# EasyDriverTip122.net
KiCad netlist of a schematic drawn in EAGLE
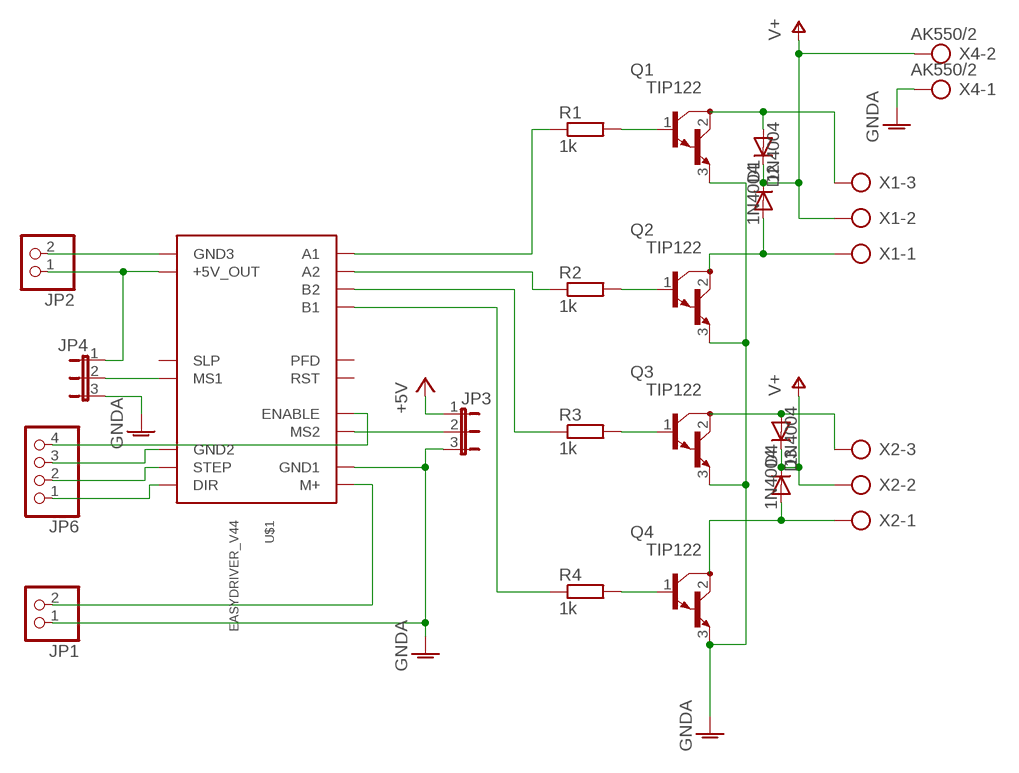
[diagram p0: schematic, sheet 1]

(export (version "E")
  (design (tool "Eeschema 10.0.6"))
  (components
    (comp (ref "D1")
      (value "1N4004")
      (footprint "eagle-import:DO41-10")
      (libsource (lib "eagle-import") (part "1N4004"))
    )
    (comp (ref "D2")
      (value "1N4004")
      (footprint "eagle-import:DO41-10")
      (libsource (lib "eagle-import") (part "1N4004"))
    )
    (comp (ref "D3")
      (value "1N4004")
      (footprint "eagle-import:DO41-10")
      (libsource (lib "eagle-import") (part "1N4004"))
    )
    (comp (ref "D4")
      (value "1N4004")
      (footprint "eagle-import:DO41-10")
      (libsource (lib "eagle-import") (part "1N4004"))
    )
    (comp (ref "JP1")
      (value "PINHD-1X2")
      (footprint "eagle-import:1X02")
      (libsource (lib "eagle-import") (part "PINHD-1X2"))
    )
    (comp (ref "JP2")
      (value "PINHD-1X2")
      (footprint "eagle-import:1X02")
      (libsource (lib "eagle-import") (part "PINHD-1X2"))
    )
    (comp (ref "JP3")
      (value "JP2E")
      (footprint "eagle-import:JP2")
      (libsource (lib "eagle-import") (part "JP2E"))
    )
    (comp (ref "JP4")
      (value "JP2E")
      (footprint "eagle-import:JP2")
      (libsource (lib "eagle-import") (part "JP2E"))
    )
    (comp (ref "JP6")
      (value "PINHD-1X4")
      (footprint "eagle-import:1X04")
      (libsource (lib "eagle-import") (part "PINHD-1X4"))
    )
    (comp (ref "Q1")
      (value "TIP122")
      (footprint "eagle-import:TO220V")
      (libsource (lib "eagle-import") (part "TIP122"))
    )
    (comp (ref "Q2")
      (value "TIP122")
      (footprint "eagle-import:TO220V")
      (libsource (lib "eagle-import") (part "TIP122"))
    )
    (comp (ref "Q3")
      (value "TIP122")
      (footprint "eagle-import:TO220V")
      (libsource (lib "eagle-import") (part "TIP122"))
    )
    (comp (ref "Q4")
      (value "TIP122")
      (footprint "eagle-import:TO220V")
      (libsource (lib "eagle-import") (part "TIP122"))
    )
    (comp (ref "R1")
      (value "1k")
      (footprint "eagle-import:0204_7")
      (libsource (lib "eagle-import") (part "R-EU_0204/7"))
    )
    (comp (ref "R2")
      (value "1k")
      (footprint "eagle-import:0204_7")
      (libsource (lib "eagle-import") (part "R-EU_0204/7"))
    )
    (comp (ref "R3")
      (value "1k")
      (footprint "eagle-import:0204_7")
      (libsource (lib "eagle-import") (part "R-EU_0204/7"))
    )
    (comp (ref "R4")
      (value "1k")
      (footprint "eagle-import:0204_7")
      (libsource (lib "eagle-import") (part "R-EU_0204/7"))
    )
    (comp (ref "U$1")
      (value "EASYDRIVER_V44")
      (footprint "eagle-import:EASYDRIVER_V44")
      (libsource (lib "eagle-import") (part "EASYDRIVER_V44"))
    )
    (comp (ref "X1")
      (value "AK500/3")
      (footprint "eagle-import:AK500_3")
      (libsource (lib "eagle-import") (part "AK500/3"))
    )
    (comp (ref "X2")
      (value "AK500/3")
      (footprint "eagle-import:AK500_3")
      (libsource (lib "eagle-import") (part "AK500/3"))
    )
    (comp (ref "X4")
      (value "AK550/2")
      (footprint "eagle-import:AK550_2")
      (libsource (lib "eagle-import") (part "AK550/2"))
    )
  )
  (nets
    (net (code "1") (name "+5V") (class "Default")
      (node (ref "JP2") (pin "1") (pinfunction "1_1") (pintype "passive"))
      (node (ref "JP3") (pin "1") (pinfunction "1_1") (pintype "passive"))
      (node (ref "JP4") (pin "1") (pinfunction "1_1") (pintype "passive"))
      (node (ref "U$1") (pin "P$11") (pinfunction "+5V_OUT_P$11") (pintype "bidirectional"))
    )
    (net (code "2") (name "GNDA") (class "Default")
      (node (ref "JP1") (pin "1") (pinfunction "1_1") (pintype "passive"))
      (node (ref "JP3") (pin "3") (pinfunction "3_3") (pintype "passive"))
      (node (ref "JP4") (pin "3") (pinfunction "3_3") (pintype "passive"))
      (node (ref "Q1") (pin "3") (pinfunction "E_3") (pintype "passive"))
      (node (ref "Q2") (pin "3") (pinfunction "E_3") (pintype "passive"))
      (node (ref "Q3") (pin "3") (pinfunction "E_3") (pintype "passive"))
      (node (ref "Q4") (pin "3") (pinfunction "E_3") (pintype "passive"))
      (node (ref "U$1") (pin "GND1") (pinfunction "GND1_GND1") (pintype "bidirectional"))
      (node (ref "X4") (pin "1") (pinfunction "KL_1") (pintype "passive"))
    )
    (net (code "3") (name "Net-(JP1-Pad2)") (class "Default")
      (node (ref "JP1") (pin "2") (pinfunction "2_2") (pintype "passive"))
      (node (ref "U$1") (pin "M+") (pinfunction "M+_M+") (pintype "bidirectional"))
    )
    (net (code "4") (name "Net-(JP2-Pad2)") (class "Default")
      (node (ref "JP2") (pin "2") (pinfunction "2_2") (pintype "passive"))
      (node (ref "U$1") (pin "GND3") (pinfunction "GND3_GND3") (pintype "bidirectional"))
    )
    (net (code "5") (name "Net-(JP3-Pad2)") (class "Default")
      (node (ref "JP3") (pin "2") (pinfunction "2_2") (pintype "passive"))
      (node (ref "U$1") (pin "MS2") (pinfunction "MS2_MS2") (pintype "bidirectional"))
    )
    (net (code "6") (name "Net-(JP4-Pad2)") (class "Default")
      (node (ref "JP4") (pin "2") (pinfunction "2_2") (pintype "passive"))
      (node (ref "U$1") (pin "MS1") (pinfunction "MS1_MS1") (pintype "bidirectional"))
    )
    (net (code "7") (name "Net-(JP6-Pad1)") (class "Default")
      (node (ref "JP6") (pin "1") (pinfunction "1_1") (pintype "passive"))
      (node (ref "U$1") (pin "DIR") (pinfunction "DIR_DIR") (pintype "bidirectional"))
    )
    (net (code "8") (name "Net-(JP6-Pad2)") (class "Default")
      (node (ref "JP6") (pin "2") (pinfunction "2_2") (pintype "passive"))
      (node (ref "U$1") (pin "STEP") (pinfunction "STEP_STEP") (pintype "bidirectional"))
    )
    (net (code "9") (name "Net-(JP6-Pad3)") (class "Default")
      (node (ref "JP6") (pin "3") (pinfunction "3_3") (pintype "passive"))
      (node (ref "U$1") (pin "GND2") (pinfunction "GND2_GND2") (pintype "bidirectional"))
    )
    (net (code "10") (name "Net-(JP6-Pad4)") (class "Default")
      (node (ref "JP6") (pin "4") (pinfunction "4_4") (pintype "passive"))
      (node (ref "U$1") (pin "ENABLE") (pinfunction "ENABLE_ENABLE") (pintype "bidirectional"))
    )
    (net (code "11") (name "Net-(Q1-B)") (class "Default")
      (node (ref "Q1") (pin "1") (pinfunction "B_1") (pintype "passive"))
      (node (ref "R1") (pin "2") (pinfunction "2_2") (pintype "passive"))
    )
    (net (code "12") (name "Net-(Q1-C)") (class "Default")
      (node (ref "D2") (pin "A") (pinfunction "A_A") (pintype "passive"))
      (node (ref "Q1") (pin "2") (pinfunction "C_2") (pintype "passive"))
      (node (ref "X1") (pin "3") (pinfunction "KL_3") (pintype "passive"))
    )
    (net (code "13") (name "Net-(Q2-B)") (class "Default")
      (node (ref "Q2") (pin "1") (pinfunction "B_1") (pintype "passive"))
      (node (ref "R2") (pin "2") (pinfunction "2_2") (pintype "passive"))
    )
    (net (code "14") (name "Net-(Q2-C)") (class "Default")
      (node (ref "D1") (pin "A") (pinfunction "A_A") (pintype "passive"))
      (node (ref "Q2") (pin "2") (pinfunction "C_2") (pintype "passive"))
      (node (ref "X1") (pin "1") (pinfunction "KL_1") (pintype "passive"))
    )
    (net (code "15") (name "Net-(Q3-B)") (class "Default")
      (node (ref "Q3") (pin "1") (pinfunction "B_1") (pintype "passive"))
      (node (ref "R3") (pin "2") (pinfunction "2_2") (pintype "passive"))
    )
    (net (code "16") (name "Net-(Q3-C)") (class "Default")
      (node (ref "D3") (pin "A") (pinfunction "A_A") (pintype "passive"))
      (node (ref "Q3") (pin "2") (pinfunction "C_2") (pintype "passive"))
      (node (ref "X2") (pin "3") (pinfunction "KL_3") (pintype "passive"))
    )
    (net (code "17") (name "Net-(Q4-B)") (class "Default")
      (node (ref "Q4") (pin "1") (pinfunction "B_1") (pintype "passive"))
      (node (ref "R4") (pin "2") (pinfunction "2_2") (pintype "passive"))
    )
    (net (code "18") (name "Net-(Q4-C)") (class "Default")
      (node (ref "D4") (pin "A") (pinfunction "A_A") (pintype "passive"))
      (node (ref "Q4") (pin "2") (pinfunction "C_2") (pintype "passive"))
      (node (ref "X2") (pin "1") (pinfunction "KL_1") (pintype "passive"))
    )
    (net (code "19") (name "Net-(R1-Pad1)") (class "Default")
      (node (ref "R1") (pin "1") (pinfunction "1_1") (pintype "passive"))
      (node (ref "U$1") (pin "A1") (pinfunction "A1_A1") (pintype "bidirectional"))
    )
    (net (code "20") (name "Net-(R2-Pad1)") (class "Default")
      (node (ref "R2") (pin "1") (pinfunction "1_1") (pintype "passive"))
      (node (ref "U$1") (pin "A2") (pinfunction "A2_A2") (pintype "bidirectional"))
    )
    (net (code "21") (name "Net-(R3-Pad1)") (class "Default")
      (node (ref "R3") (pin "1") (pinfunction "1_1") (pintype "passive"))
      (node (ref "U$1") (pin "B2") (pinfunction "B2_B2") (pintype "bidirectional"))
    )
    (net (code "22") (name "Net-(R4-Pad1)") (class "Default")
      (node (ref "R4") (pin "1") (pinfunction "1_1") (pintype "passive"))
      (node (ref "U$1") (pin "B1") (pinfunction "B1_B1") (pintype "bidirectional"))
    )
    (net (code "23") (name "V+") (class "Default")
      (node (ref "D1") (pin "C") (pinfunction "C_C") (pintype "passive"))
      (node (ref "D2") (pin "C") (pinfunction "C_C") (pintype "passive"))
      (node (ref "D3") (pin "C") (pinfunction "C_C") (pintype "passive"))
      (node (ref "D4") (pin "C") (pinfunction "C_C") (pintype "passive"))
      (node (ref "X1") (pin "2") (pinfunction "KL_2") (pintype "passive"))
      (node (ref "X2") (pin "2") (pinfunction "KL_2") (pintype "passive"))
      (node (ref "X4") (pin "2") (pinfunction "KL_2") (pintype "passive"))
    )
    (net (code "24") (name "unconnected-(U$1-PadPFD)") (class "Default")
      (node (ref "U$1") (pin "PFD") (pinfunction "PFD_PFD") (pintype "bidirectional"))
    )
    (net (code "25") (name "unconnected-(U$1-PadRST)") (class "Default")
      (node (ref "U$1") (pin "RST") (pinfunction "RST_RST") (pintype "bidirectional"))
    )
    (net (code "26") (name "unconnected-(U$1-SLP-PadSLEEP)") (class "Default")
      (node (ref "U$1") (pin "SLEEP") (pinfunction "SLP_SLEEP") (pintype "bidirectional"))
    )
  )
)
